# Sheet1.net
KiCad netlist of a schematic drawn in Altium Designer
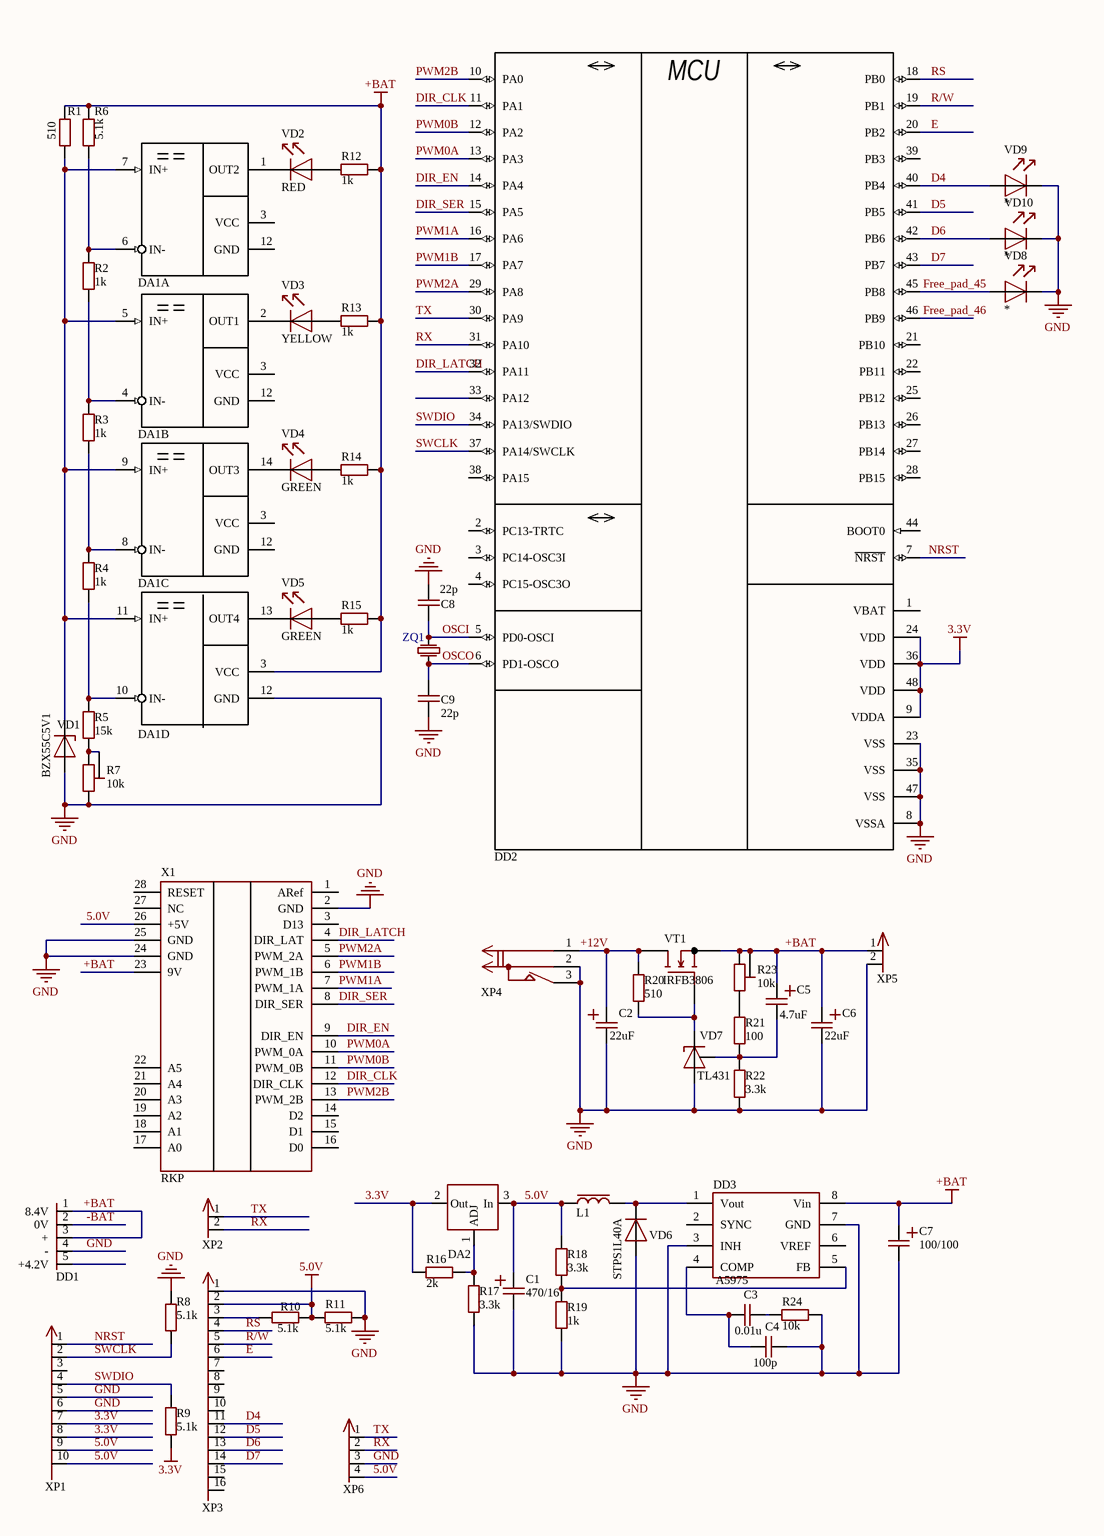
[diagram p0: Sheet1.SchDoc]

(export (version "E")
  (design (tool "Eeschema 10.0.6"))
  (components
    (comp (ref "C1") (value "470/16") (footprint "ECAP_10_5") (libsource (lib "My_LIB") (part "CAP-E")))
    (comp (ref "C2") (value "22uF") (footprint "ECAP_10_5") (libsource (lib "My_LIB") (part "CAP-E")))
    (comp (ref "C3") (value "0.01u") (footprint "C0805") (libsource (lib "My_LIB") (part "CAP")))
    (comp (ref "C4") (value "100p") (footprint "C0805") (libsource (lib "My_LIB") (part "CAP")))
    (comp (ref "C5") (value "4.7uF") (footprint "ECAP_10_5") (libsource (lib "My_LIB") (part "CAP-E")))
    (comp (ref "C6") (value "22uF") (footprint "ECAP_10_5") (libsource (lib "My_LIB") (part "CAP-E")))
    (comp (ref "C7") (value "100/100") (footprint "ECAP_10_5") (libsource (lib "My_LIB") (part "CAP-E")))
    (comp (ref "C8") (value "22p") (footprint "C0805") (libsource (lib "My_LIB") (part "CAP")))
    (comp (ref "C9") (value "22p") (footprint "C0805") (libsource (lib "My_LIB") (part "CAP")))
    (comp (ref "DA1") (value "*") (footprint "SOP14") (libsource (lib "My_LIB") (part "LM339")))
    (comp (ref "DA2") (value "LM117") (footprint "SOT-223") (libsource (lib "My_LIB") (part "LM117")))
    (comp (ref "DD1") (value "REV1.4") (footprint "20A8.4ВREV1.2") (libsource (lib "My_LIB") (part "REV1.4")))
    (comp (ref "DD2")
      (value "*")
      (footprint "LQFP-48")
      (libsource (lib "My_LIB") (part "STM32F103Cxxx-Series"))
    )
    (comp (ref "DD3")
      (value "A5975")
      (footprint "SOIC8")
      (description "STEP-DOWN")
      (libsource (lib "My_LIB") (part "A5975"))
    )
    (comp (ref "L1")
      (value "CDRH127/LDNP-220MC")
      (footprint "CDRH127")
      (libsource (lib "My_LIB") (part "Coil"))
    )
    (comp (ref "R1") (value "510") (footprint "R0805") (libsource (lib "My_LIB") (part "RES")))
    (comp (ref "R2") (value "1k") (footprint "R0805") (libsource (lib "My_LIB") (part "RES")))
    (comp (ref "R3") (value "1k") (footprint "R0805") (libsource (lib "My_LIB") (part "RES")))
    (comp (ref "R4") (value "1k") (footprint "R0805") (libsource (lib "My_LIB") (part "RES")))
    (comp (ref "R5") (value "15k") (footprint "R0805") (libsource (lib "My_LIB") (part "RES")))
    (comp (ref "R6") (value "5.1k") (footprint "R0805") (libsource (lib "My_LIB") (part "RES")))
    (comp (ref "R7") (value "10k") (footprint "T93YA") (libsource (lib "My_LIB") (part "Resistor Trimmers")))
    (comp (ref "R8") (value "5.1k") (footprint "R0805") (libsource (lib "") (part "RES_2")))
    (comp (ref "R9") (value "5.1k") (footprint "R0805") (libsource (lib "My_LIB") (part "RES")))
    (comp (ref "R10") (value "5.1k") (footprint "R0805") (libsource (lib "") (part "RES_1")))
    (comp (ref "R11") (value "5.1k") (footprint "R0805") (libsource (lib "") (part "RES_1")))
    (comp (ref "R12") (value "1k") (footprint "R0805") (libsource (lib "") (part "RES_1")))
    (comp (ref "R13") (value "1k") (footprint "R0805") (libsource (lib "") (part "RES_1")))
    (comp (ref "R14") (value "1k") (footprint "R0805") (libsource (lib "") (part "RES_1")))
    (comp (ref "R15") (value "1k") (footprint "R0805") (libsource (lib "") (part "RES_1")))
    (comp (ref "R16") (value "2k") (footprint "R0805") (libsource (lib "") (part "RES_3")))
    (comp (ref "R17") (value "3.3k") (footprint "R0805") (libsource (lib "My_LIB") (part "RES")))
    (comp (ref "R18") (value "3.3k") (footprint "R0805") (libsource (lib "My_LIB") (part "RES")))
    (comp (ref "R19") (value "1k") (footprint "R0805") (libsource (lib "My_LIB") (part "RES")))
    (comp (ref "R20") (value "510") (footprint "R0805") (libsource (lib "My_LIB") (part "RES")))
    (comp (ref "R21") (value "100") (footprint "R0805") (libsource (lib "My_LIB") (part "RES")))
    (comp (ref "R22") (value "3.3k") (footprint "R0805") (libsource (lib "My_LIB") (part "RES")))
    (comp (ref "R23") (value "10k") (footprint "T93YA") (libsource (lib "My_LIB") (part "Resistor Trimmers")))
    (comp (ref "R24") (value "10k") (footprint "R0805") (libsource (lib "") (part "RES_3")))
    (comp (ref "VD1") (value "BZX55C5V1") (footprint "DO-35") (libsource (lib "My_LIB") (part "Zender")))
    (comp (ref "VD2") (value "RED") (footprint "LED-5mm") (libsource (lib "My_LIB") (part "LED")))
    (comp (ref "VD3") (value "YELLOW") (footprint "LED-5mm") (libsource (lib "My_LIB") (part "LED")))
    (comp (ref "VD4") (value "GREEN") (footprint "LED-5mm") (libsource (lib "My_LIB") (part "LED")))
    (comp (ref "VD5") (value "GREEN") (footprint "LED-5mm") (libsource (lib "My_LIB") (part "LED")))
    (comp (ref "VD6") (value "STPS1L40A") (footprint "DO-214AC") (libsource (lib "My_LIB") (part "Diode")))
    (comp (ref "VD7") (value "TL431") (footprint "TO-92") (libsource (lib "My_LIB") (part "TL431")))
    (comp (ref "VD8") (value "*") (footprint "LED-5mm") (libsource (lib "") (part "LED_1")))
    (comp (ref "VD9") (value "*") (footprint "LED-5mm") (libsource (lib "") (part "LED_1")))
    (comp (ref "VD10") (value "*") (footprint "LED-5mm") (libsource (lib "") (part "LED_1")))
    (comp (ref "VT1") (value "IRFB3806") (footprint "TO-220+FK") (libsource (lib "My_LIB") (part "MOSFET-N")))
    (comp (ref "X1")
      (value "RKP")
      (footprint "ARDUINO SHIELD")
      (libsource (lib "My_LIB") (part "MOTOR_SHIELD"))
    )
    (comp (ref "XP1") (value "*") (footprint "IDC10M") (libsource (lib "My_LIB") (part "IDC10M")))
    (comp (ref "XP2") (value "JAMPER") (footprint "PLS-2") (libsource (lib "My_LIB") (part "CONNX2")))
    (comp (ref "XP3") (value "*") (footprint "IDC16M") (libsource (lib "My_LIB") (part "IDC16M")))
    (comp (ref "XP4") (value "*") (footprint "DJK-02-Series") (libsource (lib "My_LIB") (part "Con-2-M-DP")))
    (comp (ref "XP5") (value "JAMPER") (footprint "PLS-2") (libsource (lib "My_LIB") (part "CONNX2")))
    (comp (ref "XP6") (value "JAMPER") (footprint "PLS-4") (libsource (lib "My_LIB") (part "CONNX4")))
    (comp (ref "ZQ1") (value "*") (footprint "HC-49S") (libsource (lib "My_LIB") (part "Crystal")))
  )
  (nets
    (net (code "1") (name "+BAT") (class "Default")
      (node (ref "C5") (pin "1") (pinfunction "1_1") (pintype "passive"))
      (node (ref "C6") (pin "1") (pinfunction "1_1") (pintype "passive"))
      (node (ref "C7") (pin "1") (pinfunction "1_1") (pintype "passive"))
      (node (ref "DA1") (pin "3") (pinfunction "VCC_3") (pintype "power_in"))
      (node (ref "DD1") (pin "1") (pinfunction "8.4V_1") (pintype "passive"))
      (node (ref "DD1") (pin "3") (pinfunction "+_3") (pintype "passive"))
      (node (ref "DD3") (pin "8") (pinfunction "Vin_8") (pintype "power_in"))
      (node (ref "R1") (pin "2") (pinfunction "2_2") (pintype "passive"))
      (node (ref "R12") (pin "2") (pinfunction "2_2") (pintype "passive"))
      (node (ref "R13") (pin "2") (pinfunction "2_2") (pintype "passive"))
      (node (ref "R14") (pin "2") (pinfunction "2_2") (pintype "passive"))
      (node (ref "R15") (pin "2") (pinfunction "2_2") (pintype "passive"))
      (node (ref "R23") (pin "1") (pinfunction "1_1") (pintype "passive"))
      (node (ref "R23") (pin "2") (pinfunction "2_2") (pintype "passive"))
      (node (ref "R6") (pin "2") (pinfunction "2_2") (pintype "passive"))
      (node (ref "VT1") (pin "3") (pinfunction "S_3") (pintype "passive"))
      (node (ref "X1") (pin "23") (pinfunction "9V_23") (pintype "passive"))
      (node (ref "XP5") (pin "1") (pinfunction "1_1") (pintype "passive"))
    )
    (net (code "2") (name "/+12V") (class "Default")
      (node (ref "C2") (pin "1") (pinfunction "1_1") (pintype "passive"))
      (node (ref "R20") (pin "2") (pinfunction "2_2") (pintype "passive"))
      (node (ref "VT1") (pin "2") (pinfunction "D_2") (pintype "passive"))
      (node (ref "XP4") (pin "1") (pintype "passive"))
    )
    (net (code "3") (name "/-BAT") (class "Default")
      (node (ref "DD1") (pin "2") (pinfunction "0V_2") (pintype "passive"))
    )
    (net (code "4") (name "/D4") (class "Default")
      (node (ref "DD2") (pin "40") (pinfunction "PB4_40") (pintype "bidirectional"))
      (node (ref "VD9") (pin "1") (pinfunction "А_1") (pintype "passive"))
      (node (ref "XP3") (pin "11") (pinfunction "11_11") (pintype "passive"))
    )
    (net (code "5") (name "/D5") (class "Default")
      (node (ref "DD2") (pin "41") (pinfunction "PB5_41") (pintype "bidirectional"))
      (node (ref "XP3") (pin "12") (pinfunction "12_12") (pintype "passive"))
    )
    (net (code "6") (name "/D6") (class "Default")
      (node (ref "DD2") (pin "42") (pinfunction "PB6_42") (pintype "bidirectional"))
      (node (ref "VD10") (pin "1") (pinfunction "А_1") (pintype "passive"))
      (node (ref "XP3") (pin "13") (pinfunction "13_13") (pintype "passive"))
    )
    (net (code "7") (name "/D7") (class "Default")
      (node (ref "DD2") (pin "43") (pinfunction "PB7_43") (pintype "bidirectional"))
      (node (ref "XP3") (pin "14") (pinfunction "14_14") (pintype "passive"))
    )
    (net (code "8") (name "/DIR_CLK") (class "Default")
      (node (ref "DD2") (pin "11") (pinfunction "PA1_11") (pintype "bidirectional"))
      (node (ref "X1") (pin "12") (pinfunction "DIR_CLK_12") (pintype "passive"))
    )
    (net (code "9") (name "/DIR_EN") (class "Default")
      (node (ref "DD2") (pin "14") (pinfunction "PA4_14") (pintype "bidirectional"))
      (node (ref "X1") (pin "9") (pinfunction "DIR_EN_9") (pintype "passive"))
    )
    (net (code "10") (name "/DIR_LATCH") (class "Default")
      (node (ref "DD2") (pin "32") (pinfunction "PA11_32") (pintype "bidirectional"))
      (node (ref "X1") (pin "4") (pinfunction "DIR_LAT_4") (pintype "passive"))
    )
    (net (code "11") (name "/DIR_SER") (class "Default")
      (node (ref "DD2") (pin "15") (pinfunction "PA5_15") (pintype "bidirectional"))
      (node (ref "X1") (pin "8") (pinfunction "DIR_SER_8") (pintype "passive"))
    )
    (net (code "12") (name "/E") (class "Default")
      (node (ref "DD2") (pin "20") (pinfunction "PB2_20") (pintype "bidirectional"))
      (node (ref "XP3") (pin "6") (pinfunction "6_6") (pintype "passive"))
    )
    (net (code "13") (name "/Free_pad_45") (class "Default")
      (node (ref "DD2") (pin "45") (pinfunction "PB8_45") (pintype "bidirectional"))
      (node (ref "VD8") (pin "1") (pinfunction "А_1") (pintype "passive"))
    )
    (net (code "14") (name "/Free_pad_46") (class "Default")
      (node (ref "DD2") (pin "46") (pinfunction "PB9_46") (pintype "bidirectional"))
    )
    (net (code "15") (name "/NRST") (class "Default")
      (node (ref "DD2") (pin "7") (pinfunction "~{NRST}_7") (pintype "bidirectional"))
      (node (ref "XP1") (pin "1") (pinfunction "1_1") (pintype "passive"))
    )
    (net (code "16") (name "/OSCI") (class "Default")
      (node (ref "C8") (pin "1") (pinfunction "1_1") (pintype "passive"))
      (node (ref "DD2") (pin "5") (pinfunction "PD0-OSCI_5") (pintype "bidirectional"))
      (node (ref "ZQ1") (pin "3") (pinfunction "3_3") (pintype "passive"))
    )
    (net (code "17") (name "/OSCO") (class "Default")
      (node (ref "C9") (pin "2") (pinfunction "2_2") (pintype "passive"))
      (node (ref "DD2") (pin "6") (pinfunction "PD1-OSCO_6") (pintype "bidirectional"))
      (node (ref "ZQ1") (pin "1") (pinfunction "1_1") (pintype "passive"))
    )
    (net (code "18") (name "/PWM0A") (class "Default")
      (node (ref "DD2") (pin "13") (pinfunction "PA3_13") (pintype "bidirectional"))
      (node (ref "X1") (pin "10") (pinfunction "PWM_0A_10") (pintype "passive"))
    )
    (net (code "19") (name "/PWM0B") (class "Default")
      (node (ref "DD2") (pin "12") (pinfunction "PA2_12") (pintype "bidirectional"))
      (node (ref "X1") (pin "11") (pinfunction "PWM_0B_11") (pintype "passive"))
    )
    (net (code "20") (name "/PWM1A") (class "Default")
      (node (ref "DD2") (pin "16") (pinfunction "PA6_16") (pintype "bidirectional"))
      (node (ref "X1") (pin "7") (pinfunction "PWM_1A_7") (pintype "passive"))
    )
    (net (code "21") (name "/PWM1B") (class "Default")
      (node (ref "DD2") (pin "17") (pinfunction "PA7_17") (pintype "bidirectional"))
      (node (ref "X1") (pin "6") (pinfunction "PWM_1B_6") (pintype "passive"))
    )
    (net (code "22") (name "/PWM2A") (class "Default")
      (node (ref "DD2") (pin "29") (pinfunction "PA8_29") (pintype "bidirectional"))
      (node (ref "X1") (pin "5") (pinfunction "PWM_2A_5") (pintype "passive"))
    )
    (net (code "23") (name "/PWM2B") (class "Default")
      (node (ref "DD2") (pin "10") (pinfunction "PA0_10") (pintype "bidirectional"))
      (node (ref "X1") (pin "13") (pinfunction "PWM_2B_13") (pintype "passive"))
    )
    (net (code "24") (name "/RS") (class "Default")
      (node (ref "DD2") (pin "18") (pinfunction "PB0_18") (pintype "bidirectional"))
      (node (ref "XP3") (pin "4") (pinfunction "4_4") (pintype "passive"))
    )
    (net (code "25") (name "/RX") (class "Default")
      (node (ref "DD2") (pin "31") (pinfunction "PA10_31") (pintype "bidirectional"))
      (node (ref "XP2") (pin "2") (pinfunction "2_2") (pintype "passive"))
      (node (ref "XP6") (pin "2") (pinfunction "2_2") (pintype "passive"))
    )
    (net (code "26") (name "/R{slash}W") (class "Default")
      (node (ref "DD2") (pin "19") (pinfunction "PB1_19") (pintype "bidirectional"))
      (node (ref "XP3") (pin "5") (pinfunction "5_5") (pintype "passive"))
    )
    (net (code "27") (name "/SWCLK") (class "Default")
      (node (ref "DD2") (pin "37") (pinfunction "PA14/SWCLK_37") (pintype "bidirectional"))
      (node (ref "R8") (pin "2") (pinfunction "2_2") (pintype "passive"))
      (node (ref "XP1") (pin "2") (pinfunction "2_2") (pintype "passive"))
    )
    (net (code "28") (name "/SWDIO") (class "Default")
      (node (ref "DD2") (pin "34") (pinfunction "PA13/SWDIO_34") (pintype "bidirectional"))
      (node (ref "R9") (pin "2") (pinfunction "2_2") (pintype "passive"))
      (node (ref "XP1") (pin "4") (pinfunction "4_4") (pintype "passive"))
    )
    (net (code "29") (name "/TX") (class "Default")
      (node (ref "DD2") (pin "30") (pinfunction "PA9_30") (pintype "bidirectional"))
      (node (ref "XP2") (pin "1") (pinfunction "1_1") (pintype "passive"))
      (node (ref "XP6") (pin "1") (pinfunction "1_1") (pintype "passive"))
    )
    (net (code "30") (name "3.3V") (class "Default")
      (node (ref "DA2") (pin "2") (pinfunction "Out_2") (pintype "passive"))
      (node (ref "DD2") (pin "24") (pinfunction "VDD_24") (pintype "power_in"))
      (node (ref "DD2") (pin "36") (pinfunction "VDD_36") (pintype "power_in"))
      (node (ref "DD2") (pin "48") (pinfunction "VDD_48") (pintype "power_in"))
      (node (ref "DD2") (pin "9") (pinfunction "VDDA_9") (pintype "power_in"))
      (node (ref "R16") (pin "2") (pinfunction "2_2") (pintype "passive"))
      (node (ref "R9") (pin "1") (pinfunction "1_1") (pintype "passive"))
      (node (ref "XP1") (pin "7") (pinfunction "7_7") (pintype "passive"))
      (node (ref "XP1") (pin "8") (pinfunction "8_8") (pintype "passive"))
    )
    (net (code "31") (name "5.0V") (class "Default")
      (node (ref "C1") (pin "1") (pinfunction "1_1") (pintype "passive"))
      (node (ref "DA2") (pin "3") (pinfunction "In_3") (pintype "passive"))
      (node (ref "L1") (pin "1") (pinfunction "1_1") (pintype "passive"))
      (node (ref "R10") (pin "2") (pinfunction "2_2") (pintype "passive"))
      (node (ref "R11") (pin "1") (pinfunction "1_1") (pintype "passive"))
      (node (ref "R18") (pin "2") (pinfunction "2_2") (pintype "passive"))
      (node (ref "X1") (pin "26") (pinfunction "+5V_26") (pintype "passive"))
      (node (ref "XP1") (pin "10") (pinfunction "10_10") (pintype "passive"))
      (node (ref "XP1") (pin "9") (pinfunction "9_9") (pintype "passive"))
      (node (ref "XP3") (pin "2") (pinfunction "2_2") (pintype "passive"))
      (node (ref "XP6") (pin "4") (pinfunction "4_4") (pintype "passive"))
    )
    (net (code "32") (name "GND") (class "Default")
      (node (ref "C1") (pin "2") (pinfunction "2_2") (pintype "passive"))
      (node (ref "C2") (pin "2") (pinfunction "2_2") (pintype "passive"))
      (node (ref "C4") (pin "1") (pinfunction "1_1") (pintype "passive"))
      (node (ref "C6") (pin "2") (pinfunction "2_2") (pintype "passive"))
      (node (ref "C7") (pin "2") (pinfunction "2_2") (pintype "passive"))
      (node (ref "C8") (pin "2") (pinfunction "2_2") (pintype "passive"))
      (node (ref "C9") (pin "1") (pinfunction "1_1") (pintype "passive"))
      (node (ref "DA1") (pin "12") (pinfunction "GND_12") (pintype "power_in"))
      (node (ref "DD1") (pin "4") (pinfunction "-_4") (pintype "passive"))
      (node (ref "DD2") (pin "23") (pinfunction "VSS_23") (pintype "power_in"))
      (node (ref "DD2") (pin "35") (pinfunction "VSS_35") (pintype "power_in"))
      (node (ref "DD2") (pin "47") (pinfunction "VSS_47") (pintype "power_in"))
      (node (ref "DD2") (pin "8") (pinfunction "VSSA_8") (pintype "power_in"))
      (node (ref "DD3") (pin "3") (pinfunction "INH_3") (pintype "power_in"))
      (node (ref "DD3") (pin "7") (pinfunction "GND_7") (pintype "power_in"))
      (node (ref "R11") (pin "2") (pinfunction "2_2") (pintype "passive"))
      (node (ref "R17") (pin "1") (pinfunction "1_1") (pintype "passive"))
      (node (ref "R19") (pin "1") (pinfunction "1_1") (pintype "passive"))
      (node (ref "R22") (pin "1") (pinfunction "1_1") (pintype "passive"))
      (node (ref "R24") (pin "1") (pinfunction "1_1") (pintype "passive"))
      (node (ref "R7") (pin "3") (pinfunction "3_3") (pintype "passive"))
      (node (ref "R8") (pin "1") (pinfunction "1_1") (pintype "passive"))
      (node (ref "VD1") (pin "1") (pinfunction "А_1") (pintype "passive"))
      (node (ref "VD10") (pin "2") (pinfunction "К_2") (pintype "passive"))
      (node (ref "VD6") (pin "1") (pinfunction "А_1") (pintype "passive"))
      (node (ref "VD7") (pin "2") (pinfunction "А_2") (pintype "passive"))
      (node (ref "VD8") (pin "2") (pinfunction "К_2") (pintype "passive"))
      (node (ref "VD9") (pin "2") (pinfunction "К_2") (pintype "passive"))
      (node (ref "X1") (pin "2") (pinfunction "GND_2") (pintype "passive"))
      (node (ref "X1") (pin "24") (pinfunction "GND_24") (pintype "passive"))
      (node (ref "X1") (pin "25") (pinfunction "GND_25") (pintype "passive"))
      (node (ref "XP1") (pin "5") (pinfunction "5_5") (pintype "passive"))
      (node (ref "XP1") (pin "6") (pinfunction "6_6") (pintype "passive"))
      (node (ref "XP3") (pin "1") (pinfunction "1_1") (pintype "passive"))
      (node (ref "XP4") (pin "2") (pintype "passive"))
      (node (ref "XP4") (pin "3") (pintype "passive"))
      (node (ref "XP5") (pin "2") (pinfunction "2_2") (pintype "passive"))
      (node (ref "XP6") (pin "3") (pinfunction "3_3") (pintype "passive"))
    )
    (net (code "33") (name "Net-(C3-Pad1)") (class "Default")
      (node (ref "C3") (pin "1") (pinfunction "1_1") (pintype "passive"))
      (node (ref "R24") (pin "2") (pinfunction "2_2") (pintype "passive"))
    )
    (net (code "34") (name "Net-(DA1A-IN+)") (class "Default")
      (node (ref "DA1") (pin "11") (pinfunction "IN+_11") (pintype "input"))
      (node (ref "DA1") (pin "5") (pinfunction "IN+_5") (pintype "input"))
      (node (ref "DA1") (pin "7") (pinfunction "IN+_7") (pintype "input"))
      (node (ref "DA1") (pin "9") (pinfunction "IN+_9") (pintype "input"))
      (node (ref "R1") (pin "1") (pinfunction "1_1") (pintype "passive"))
      (node (ref "VD1") (pin "2") (pinfunction "К_2") (pintype "passive"))
    )
    (net (code "35") (name "Net-(DA1A-IN-)") (class "Default")
      (node (ref "DA1") (pin "6") (pinfunction "IN-_6") (pintype "input"))
      (node (ref "R2") (pin "2") (pinfunction "2_2") (pintype "passive"))
      (node (ref "R6") (pin "1") (pinfunction "1_1") (pintype "passive"))
    )
    (net (code "36") (name "Net-(DA1A-OUT2)") (class "Default")
      (node (ref "DA1") (pin "1") (pinfunction "OUT2_1") (pintype "open_collector"))
      (node (ref "VD2") (pin "2") (pinfunction "К_2") (pintype "passive"))
    )
    (net (code "37") (name "Net-(DA1B-IN-)") (class "Default")
      (node (ref "DA1") (pin "4") (pinfunction "IN-_4") (pintype "input"))
      (node (ref "R2") (pin "1") (pinfunction "1_1") (pintype "passive"))
      (node (ref "R3") (pin "2") (pinfunction "2_2") (pintype "passive"))
    )
    (net (code "38") (name "Net-(DA1B-OUT1)") (class "Default")
      (node (ref "DA1") (pin "2") (pinfunction "OUT1_2") (pintype "open_collector"))
      (node (ref "VD3") (pin "2") (pinfunction "К_2") (pintype "passive"))
    )
    (net (code "39") (name "Net-(DA1C-IN-)") (class "Default")
      (node (ref "DA1") (pin "8") (pinfunction "IN-_8") (pintype "input"))
      (node (ref "R3") (pin "1") (pinfunction "1_1") (pintype "passive"))
      (node (ref "R4") (pin "2") (pinfunction "2_2") (pintype "passive"))
    )
    (net (code "40") (name "Net-(DA1C-OUT3)") (class "Default")
      (node (ref "DA1") (pin "14") (pinfunction "OUT3_14") (pintype "open_collector"))
      (node (ref "VD4") (pin "2") (pinfunction "К_2") (pintype "passive"))
    )
    (net (code "41") (name "Net-(DA1D-IN-)") (class "Default")
      (node (ref "DA1") (pin "10") (pinfunction "IN-_10") (pintype "input"))
      (node (ref "R4") (pin "1") (pinfunction "1_1") (pintype "passive"))
      (node (ref "R5") (pin "2") (pinfunction "2_2") (pintype "passive"))
    )
    (net (code "42") (name "Net-(DA1D-OUT4)") (class "Default")
      (node (ref "DA1") (pin "13") (pinfunction "OUT4_13") (pintype "open_collector"))
      (node (ref "VD5") (pin "2") (pinfunction "К_2") (pintype "passive"))
    )
    (net (code "43") (name "Net-(DA2-ADJ)") (class "Default")
      (node (ref "DA2") (pin "1") (pinfunction "ADJ_1") (pintype "passive"))
      (node (ref "R16") (pin "1") (pinfunction "1_1") (pintype "passive"))
      (node (ref "R17") (pin "2") (pinfunction "2_2") (pintype "passive"))
    )
    (net (code "44") (name "Net-(DD3-COMP)") (class "Default")
      (node (ref "C3") (pin "2") (pinfunction "2_2") (pintype "passive"))
      (node (ref "C4") (pin "2") (pinfunction "2_2") (pintype "passive"))
      (node (ref "DD3") (pin "4") (pinfunction "COMP_4") (pintype "passive"))
    )
    (net (code "45") (name "Net-(DD3-FB)") (class "Default")
      (node (ref "DD3") (pin "5") (pinfunction "FB_5") (pintype "passive"))
      (node (ref "R18") (pin "1") (pinfunction "1_1") (pintype "passive"))
      (node (ref "R19") (pin "2") (pinfunction "2_2") (pintype "passive"))
    )
    (net (code "46") (name "Net-(DD3-Vout)") (class "Default")
      (node (ref "DD3") (pin "1") (pinfunction "Vout_1") (pintype "power_in"))
      (node (ref "L1") (pin "2") (pinfunction "2_2") (pintype "passive"))
      (node (ref "VD6") (pin "2") (pinfunction "К_2") (pintype "passive"))
    )
    (net (code "47") (name "Net-(R5-Pad1)") (class "Default")
      (node (ref "R5") (pin "1") (pinfunction "1_1") (pintype "passive"))
      (node (ref "R7") (pin "1") (pinfunction "1_1") (pintype "passive"))
      (node (ref "R7") (pin "2") (pinfunction "2_2") (pintype "passive"))
    )
    (net (code "48") (name "Net-(R10-Pad1)") (class "Default")
      (node (ref "R10") (pin "1") (pinfunction "1_1") (pintype "passive"))
      (node (ref "XP3") (pin "3") (pinfunction "3_3") (pintype "passive"))
    )
    (net (code "49") (name "Net-(R21-Pad2)") (class "Default")
      (node (ref "R21") (pin "2") (pinfunction "2_2") (pintype "passive"))
      (node (ref "R23") (pin "3") (pinfunction "3_3") (pintype "passive"))
    )
    (net (code "50") (name "Net-(VD2-А)") (class "Default")
      (node (ref "R12") (pin "1") (pinfunction "1_1") (pintype "passive"))
      (node (ref "VD2") (pin "1") (pinfunction "А_1") (pintype "passive"))
    )
    (net (code "51") (name "Net-(VD3-А)") (class "Default")
      (node (ref "R13") (pin "1") (pinfunction "1_1") (pintype "passive"))
      (node (ref "VD3") (pin "1") (pinfunction "А_1") (pintype "passive"))
    )
    (net (code "52") (name "Net-(VD4-А)") (class "Default")
      (node (ref "R14") (pin "1") (pinfunction "1_1") (pintype "passive"))
      (node (ref "VD4") (pin "1") (pinfunction "А_1") (pintype "passive"))
    )
    (net (code "53") (name "Net-(VD5-А)") (class "Default")
      (node (ref "R15") (pin "1") (pinfunction "1_1") (pintype "passive"))
      (node (ref "VD5") (pin "1") (pinfunction "А_1") (pintype "passive"))
    )
    (net (code "54") (name "Net-(VD7-R)") (class "Default")
      (node (ref "C5") (pin "2") (pinfunction "2_2") (pintype "passive"))
      (node (ref "R21") (pin "1") (pinfunction "1_1") (pintype "passive"))
      (node (ref "R22") (pin "2") (pinfunction "2_2") (pintype "passive"))
      (node (ref "VD7") (pin "3") (pinfunction "R_3") (pintype "passive"))
    )
    (net (code "55") (name "Net-(VD7-К)") (class "Default")
      (node (ref "R20") (pin "1") (pinfunction "1_1") (pintype "passive"))
      (node (ref "VD7") (pin "1") (pinfunction "К_1") (pintype "passive"))
      (node (ref "VT1") (pin "1") (pinfunction "G_1") (pintype "passive"))
    )
    (net (code "56") (name "unconnected-(DA1A-GND-Pad12)") (class "Default")
      (node (ref "DA1") (pin "12") (pinfunction "GND_12") (pintype "power_in"))
    )
    (net (code "57") (name "unconnected-(DA1A-VCC-Pad3)") (class "Default")
      (node (ref "DA1") (pin "3") (pinfunction "VCC_3") (pintype "power_in"))
    )
    (net (code "58") (name "unconnected-(DA1B-GND-Pad12)") (class "Default")
      (node (ref "DA1") (pin "12") (pinfunction "GND_12") (pintype "power_in"))
    )
    (net (code "59") (name "unconnected-(DA1B-VCC-Pad3)") (class "Default")
      (node (ref "DA1") (pin "3") (pinfunction "VCC_3") (pintype "power_in"))
    )
    (net (code "60") (name "unconnected-(DA1C-GND-Pad12)") (class "Default")
      (node (ref "DA1") (pin "12") (pinfunction "GND_12") (pintype "power_in"))
    )
    (net (code "61") (name "unconnected-(DA1C-VCC-Pad3)") (class "Default")
      (node (ref "DA1") (pin "3") (pinfunction "VCC_3") (pintype "power_in"))
    )
    (net (code "62") (name "unconnected-(DD1-+4.2V-Pad5)") (class "Default")
      (node (ref "DD1") (pin "5") (pinfunction "+4.2V_5") (pintype "passive"))
    )
    (net (code "63") (name "unconnected-(DD2-BOOT0-Pad44)") (class "Default")
      (node (ref "DD2") (pin "44") (pinfunction "BOOT0_44") (pintype "input"))
    )
    (net (code "64") (name "unconnected-(DD2-PA12-Pad33)") (class "Default")
      (node (ref "DD2") (pin "33") (pinfunction "PA12_33") (pintype "bidirectional"))
    )
    (net (code "65") (name "unconnected-(DD2-PA15-Pad38)") (class "Default")
      (node (ref "DD2") (pin "38") (pinfunction "PA15_38") (pintype "bidirectional"))
    )
    (net (code "66") (name "unconnected-(DD2-PB3-Pad39)") (class "Default")
      (node (ref "DD2") (pin "39") (pinfunction "PB3_39") (pintype "bidirectional"))
    )
    (net (code "67") (name "unconnected-(DD2-PB10-Pad21)") (class "Default")
      (node (ref "DD2") (pin "21") (pinfunction "PB10_21") (pintype "bidirectional"))
    )
    (net (code "68") (name "unconnected-(DD2-PB11-Pad22)") (class "Default")
      (node (ref "DD2") (pin "22") (pinfunction "PB11_22") (pintype "bidirectional"))
    )
    (net (code "69") (name "unconnected-(DD2-PB12-Pad25)") (class "Default")
      (node (ref "DD2") (pin "25") (pinfunction "PB12_25") (pintype "bidirectional"))
    )
    (net (code "70") (name "unconnected-(DD2-PB13-Pad26)") (class "Default")
      (node (ref "DD2") (pin "26") (pinfunction "PB13_26") (pintype "bidirectional"))
    )
    (net (code "71") (name "unconnected-(DD2-PB14-Pad27)") (class "Default")
      (node (ref "DD2") (pin "27") (pinfunction "PB14_27") (pintype "bidirectional"))
    )
    (net (code "72") (name "unconnected-(DD2-PB15-Pad28)") (class "Default")
      (node (ref "DD2") (pin "28") (pinfunction "PB15_28") (pintype "bidirectional"))
    )
    (net (code "73") (name "unconnected-(DD2-PC13-TRTC-Pad2)") (class "Default")
      (node (ref "DD2") (pin "2") (pinfunction "PC13-TRTC_2") (pintype "bidirectional"))
    )
    (net (code "74") (name "unconnected-(DD2-PC14-OSC3I-Pad3)") (class "Default")
      (node (ref "DD2") (pin "3") (pinfunction "PC14-OSC3I_3") (pintype "bidirectional"))
    )
    (net (code "75") (name "unconnected-(DD2-PC15-OSC3O-Pad4)") (class "Default")
      (node (ref "DD2") (pin "4") (pinfunction "PC15-OSC3O_4") (pintype "bidirectional"))
    )
    (net (code "76") (name "unconnected-(DD2-VBAT-Pad1)") (class "Default")
      (node (ref "DD2") (pin "1") (pinfunction "VBAT_1") (pintype "power_in"))
    )
    (net (code "77") (name "unconnected-(DD3-SYNC-Pad2)") (class "Default")
      (node (ref "DD3") (pin "2") (pinfunction "SYNC_2") (pintype "power_in"))
    )
    (net (code "78") (name "unconnected-(DD3-VREF-Pad6)") (class "Default")
      (node (ref "DD3") (pin "6") (pinfunction "VREF_6") (pintype "power_in"))
    )
    (net (code "79") (name "unconnected-(X1-A0-Pad17)") (class "Default")
      (node (ref "X1") (pin "17") (pinfunction "A0_17") (pintype "passive"))
    )
    (net (code "80") (name "unconnected-(X1-A1-Pad18)") (class "Default")
      (node (ref "X1") (pin "18") (pinfunction "A1_18") (pintype "passive"))
    )
    (net (code "81") (name "unconnected-(X1-A2-Pad19)") (class "Default")
      (node (ref "X1") (pin "19") (pinfunction "A2_19") (pintype "passive"))
    )
    (net (code "82") (name "unconnected-(X1-A3-Pad20)") (class "Default")
      (node (ref "X1") (pin "20") (pinfunction "A3_20") (pintype "passive"))
    )
    (net (code "83") (name "unconnected-(X1-A4-Pad21)") (class "Default")
      (node (ref "X1") (pin "21") (pinfunction "A4_21") (pintype "passive"))
    )
    (net (code "84") (name "unconnected-(X1-A5-Pad22)") (class "Default")
      (node (ref "X1") (pin "22") (pinfunction "A5_22") (pintype "passive"))
    )
    (net (code "85") (name "unconnected-(X1-ARef-Pad1)") (class "Default")
      (node (ref "X1") (pin "1") (pinfunction "ARef_1") (pintype "passive"))
    )
    (net (code "86") (name "unconnected-(X1-D0-Pad16)") (class "Default")
      (node (ref "X1") (pin "16") (pinfunction "D0_16") (pintype "passive"))
    )
    (net (code "87") (name "unconnected-(X1-D1-Pad15)") (class "Default")
      (node (ref "X1") (pin "15") (pinfunction "D1_15") (pintype "passive"))
    )
    (net (code "88") (name "unconnected-(X1-D2-Pad14)") (class "Default")
      (node (ref "X1") (pin "14") (pinfunction "D2_14") (pintype "passive"))
    )
    (net (code "89") (name "unconnected-(X1-D13-Pad3)") (class "Default")
      (node (ref "X1") (pin "3") (pinfunction "D13_3") (pintype "passive"))
    )
    (net (code "90") (name "unconnected-(X1-NC-Pad27)") (class "Default")
      (node (ref "X1") (pin "27") (pinfunction "NC_27") (pintype "passive"))
    )
    (net (code "91") (name "unconnected-(X1-RESET-Pad28)") (class "Default")
      (node (ref "X1") (pin "28") (pinfunction "RESET_28") (pintype "passive"))
    )
    (net (code "92") (name "unconnected-(XP1-Pad3)") (class "Default")
      (node (ref "XP1") (pin "3") (pinfunction "3_3") (pintype "passive"))
    )
    (net (code "93") (name "unconnected-(XP3-Pad7)") (class "Default")
      (node (ref "XP3") (pin "7") (pinfunction "7_7") (pintype "passive"))
    )
    (net (code "94") (name "unconnected-(XP3-Pad8)") (class "Default")
      (node (ref "XP3") (pin "8") (pinfunction "8_8") (pintype "passive"))
    )
    (net (code "95") (name "unconnected-(XP3-Pad9)") (class "Default")
      (node (ref "XP3") (pin "9") (pinfunction "9_9") (pintype "passive"))
    )
    (net (code "96") (name "unconnected-(XP3-Pad10)") (class "Default")
      (node (ref "XP3") (pin "10") (pinfunction "10_10") (pintype "passive"))
    )
    (net (code "97") (name "unconnected-(XP3-Pad15)") (class "Default")
      (node (ref "XP3") (pin "15") (pinfunction "15_15") (pintype "passive"))
    )
    (net (code "98") (name "unconnected-(XP3-Pad16)") (class "Default")
      (node (ref "XP3") (pin "16") (pinfunction "16_16") (pintype "passive"))
    )
  )
)
